# Controle_do_Motor.net
KiCad netlist of a schematic drawn in Altium Designer
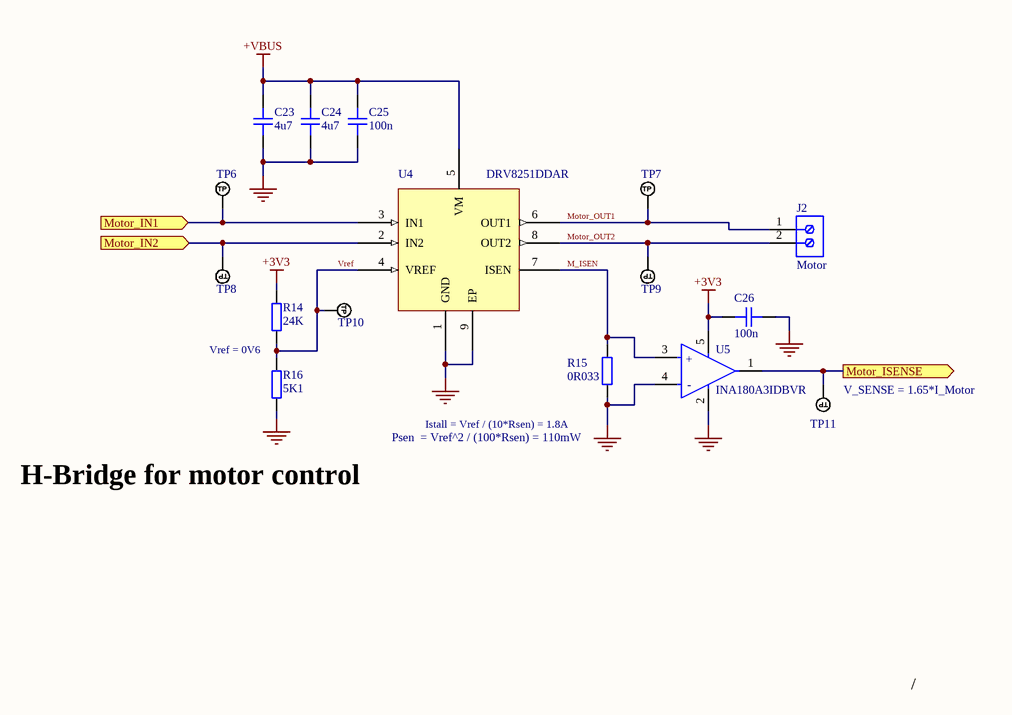
[diagram p0: Controle do Motor.SchDoc]

(export (version "E")
  (design (tool "Eeschema 10.0.6"))
  (components
    (comp (ref "C23")
      (value "4u7")
      (footprint "CAP_0805")
      (description "4.7uF ±10% 50V Ceramic Capacitor X5R 0805")
      (fields
        (field (name "MANUFACTURER") "Samsung Electro-Mechanics")
        (field (name "MANUFACTURER PART NUMBER") "CL21A475KBQNNNE")
      )
      (libsource (lib "Schematic-Lib-PhilsLab") (part "CAP_0805"))
    )
    (comp (ref "C24")
      (value "4u7")
      (footprint "CAP_0805")
      (description "4.7uF ±10% 50V Ceramic Capacitor X5R 0805")
      (fields
        (field (name "MANUFACTURER") "Samsung Electro-Mechanics")
        (field (name "MANUFACTURER PART NUMBER") "CL21A475KBQNNNE")
      )
      (libsource (lib "Schematic-Lib-PhilsLab") (part "CAP_0805"))
    )
    (comp (ref "C25")
      (value "100n")
      (footprint "CAP_0402")
      (description "100nF ±10% 50V Ceramic Capacitor X7R 0402D 0402")
      (fields
        (field (name "MANUFACTURER") "muRata")
        (field (name "MANUFACTURER PART NUMBER") "GRM155R71H104KE14D")
      )
      (libsource (lib "Schematic-Lib-PhilsLab") (part "CAP_0402"))
    )
    (comp (ref "C26")
      (value "100n")
      (footprint "CAP_0402")
      (description "100nF ±10% 50V Ceramic Capacitor X7R 0402D 0402")
      (fields
        (field (name "MANUFACTURER") "muRata")
        (field (name "MANUFACTURER PART NUMBER") "GRM155R71H104KE14D")
      )
      (libsource (lib "Schematic-Lib-PhilsLab") (part "CAP_0402"))
    )
    (comp (ref "J2")
      (value "Motor")
      (footprint "691102710002")
      (description "102 Series 5MM Pitch Straight, Pcb Terminal Block, Through Hole, 2 Way")
      (fields (field (name "VOLTAGE") "300V"))
      (libsource (lib "Altium Content Vault") (part "TBL - 1R - 02P - Screw"))
    )
    (comp (ref "R14")
      (value "24K")
      (footprint "RES_0402")
      (description "Resistor SMD 0402")
      (libsource (lib "Schematic-Lib-PhilsLab") (part "RES_0402"))
    )
    (comp (ref "R15")
      (value "0R033")
      (footprint "RES_1206")
      (description "250mW 33mΩ Thick Film Resistor ±1200ppm/℃ ±1% 1206 Chip Resistor - Surface Mount RoHS")
      (fields
        (field (name "MANUFACTURER") "FOJAN")
        (field (name "MANUFACTURER PART NUMBER") "FRL1206FR033TS")
      )
      (libsource (lib "Schematic-Lib-PhilsLab") (part "RES_1206"))
    )
    (comp (ref "R16")
      (value "5K1")
      (footprint "RES_0402")
      (description "Resistor SMD 0402")
      (libsource (lib "Schematic-Lib-PhilsLab") (part "RES_0402"))
    )
    (comp (ref "TP6")
      (value "TP_NOBOM")
      (footprint "PAD_RND_1MM")
      (description "Test Point Round 1mm (NO BOM)")
      (libsource (lib "Schematic-Lib-PhilsLab") (part "TEST_POINT_RND_1MM"))
    )
    (comp (ref "TP7")
      (value "TP_NOBOM")
      (footprint "PAD_RND_1MM")
      (description "Test Point Round 1mm (NO BOM)")
      (libsource (lib "Schematic-Lib-PhilsLab") (part "TEST_POINT_RND_1MM"))
    )
    (comp (ref "TP8")
      (value "TP_NOBOM")
      (footprint "PAD_RND_1MM")
      (description "Test Point Round 1mm (NO BOM)")
      (libsource (lib "Schematic-Lib-PhilsLab") (part "TEST_POINT_RND_1MM"))
    )
    (comp (ref "TP9")
      (value "TP_NOBOM")
      (footprint "PAD_RND_1MM")
      (description "Test Point Round 1mm (NO BOM)")
      (libsource (lib "Schematic-Lib-PhilsLab") (part "TEST_POINT_RND_1MM"))
    )
    (comp (ref "TP10")
      (value "TP_NOBOM")
      (footprint "PAD_RND_1MM")
      (description "Test Point Round 1mm (NO BOM)")
      (libsource (lib "Schematic-Lib-PhilsLab") (part "TEST_POINT_RND_1MM"))
    )
    (comp (ref "TP11")
      (value "TP_NOBOM")
      (footprint "PAD_RND_1MM")
      (description "Test Point Round 1mm (NO BOM)")
      (libsource (lib "Schematic-Lib-PhilsLab") (part "TEST_POINT_RND_1MM"))
    )
    (comp (ref "U4")
      (value "DRV8251DDAR")
      (footprint "HSOP8")
      (description "4.1-A Brushed DC Motor Driver with Integrated Current Regulation")
      (fields (field (name "MANUFACTURER") "TI"))
      (libsource (lib "Schematic-Lib-PhilsLab") (part "DRV8251"))
    )
    (comp (ref "U5")
      (value "INA180A3IDBVR")
      (footprint "FP-DBV0005A-MFG")
      (description "IC CURR SENSE 1 CIRCUIT SOT23-5")
      (libsource (lib "Altium Content Vault") (part "0a55cf1a948ad01a3239aec1b7efad0"))
    )
  )
  (nets
    (net (code "1") (name "+3V3") (class "Default")
      (node (ref "C26") (pin "2") (pinfunction "2_2") (pintype "passive"))
      (node (ref "R14") (pin "2") (pinfunction "2_2") (pintype "passive"))
      (node (ref "U5") (pin "5") (pinfunction "VS_5") (pintype "power_in"))
    )
    (net (code "2") (name "+VBUS") (class "Default")
      (node (ref "C23") (pin "2") (pinfunction "2_2") (pintype "passive"))
      (node (ref "C24") (pin "2") (pinfunction "2_2") (pintype "passive"))
      (node (ref "C25") (pin "2") (pinfunction "2_2") (pintype "passive"))
      (node (ref "U4") (pin "5") (pinfunction "VM_5") (pintype "power_in"))
    )
    (net (code "3") (name "/M_ISEN") (class "Default")
      (node (ref "R15") (pin "2") (pinfunction "2_2") (pintype "passive"))
      (node (ref "U4") (pin "7") (pinfunction "ISEN_7") (pintype "power_in"))
      (node (ref "U5") (pin "3") (pinfunction "IN+_3") (pintype "tri_state"))
    )
    (net (code "4") (name "/Motor_IN1") (class "Default")
      (node (ref "TP6") (pin "1") (pinfunction "TP_1") (pintype "passive"))
      (node (ref "U4") (pin "3") (pinfunction "IN1_3") (pintype "input"))
    )
    (net (code "5") (name "/Motor_IN2") (class "Default")
      (node (ref "TP8") (pin "1") (pinfunction "TP_1") (pintype "passive"))
      (node (ref "U4") (pin "2") (pinfunction "IN2_2") (pintype "input"))
    )
    (net (code "6") (name "/Motor_ISENSE") (class "Default")
      (node (ref "TP11") (pin "1") (pinfunction "TP_1") (pintype "passive"))
      (node (ref "U5") (pin "1") (pinfunction "OUT_1") (pintype "power_in"))
    )
    (net (code "7") (name "/Motor_OUT1") (class "Default")
      (node (ref "J2") (pin "1") (pinfunction "1_1") (pintype "passive"))
      (node (ref "TP7") (pin "1") (pinfunction "TP_1") (pintype "passive"))
      (node (ref "U4") (pin "6") (pinfunction "OUT1_6") (pintype "output"))
    )
    (net (code "8") (name "/Motor_OUT2") (class "Default")
      (node (ref "J2") (pin "2") (pinfunction "2_2") (pintype "passive"))
      (node (ref "TP9") (pin "1") (pinfunction "TP_1") (pintype "passive"))
      (node (ref "U4") (pin "8") (pinfunction "OUT2_8") (pintype "output"))
    )
    (net (code "9") (name "/Vref") (class "Default")
      (node (ref "R14") (pin "1") (pinfunction "1_1") (pintype "passive"))
      (node (ref "R16") (pin "2") (pinfunction "2_2") (pintype "passive"))
      (node (ref "TP10") (pin "1") (pinfunction "TP_1") (pintype "passive"))
      (node (ref "U4") (pin "4") (pinfunction "VREF_4") (pintype "input"))
    )
    (net (code "10") (name "GND") (class "Default")
      (node (ref "C23") (pin "1") (pinfunction "1_1") (pintype "passive"))
      (node (ref "C24") (pin "1") (pinfunction "1_1") (pintype "passive"))
      (node (ref "C25") (pin "1") (pinfunction "1_1") (pintype "passive"))
      (node (ref "C26") (pin "1") (pinfunction "1_1") (pintype "passive"))
      (node (ref "R15") (pin "1") (pinfunction "1_1") (pintype "passive"))
      (node (ref "R16") (pin "1") (pinfunction "1_1") (pintype "passive"))
      (node (ref "U4") (pin "1") (pinfunction "GND_1") (pintype "power_in"))
      (node (ref "U4") (pin "9") (pinfunction "EP_9") (pintype "power_in"))
      (node (ref "U5") (pin "2") (pinfunction "GND_2") (pintype "power_in"))
      (node (ref "U5") (pin "4") (pinfunction "IN-_4") (pintype "tri_state"))
    )
  )
)
